# boardv2AnalogConnectors.net
KiCad netlist of a schematic drawn in EAGLE
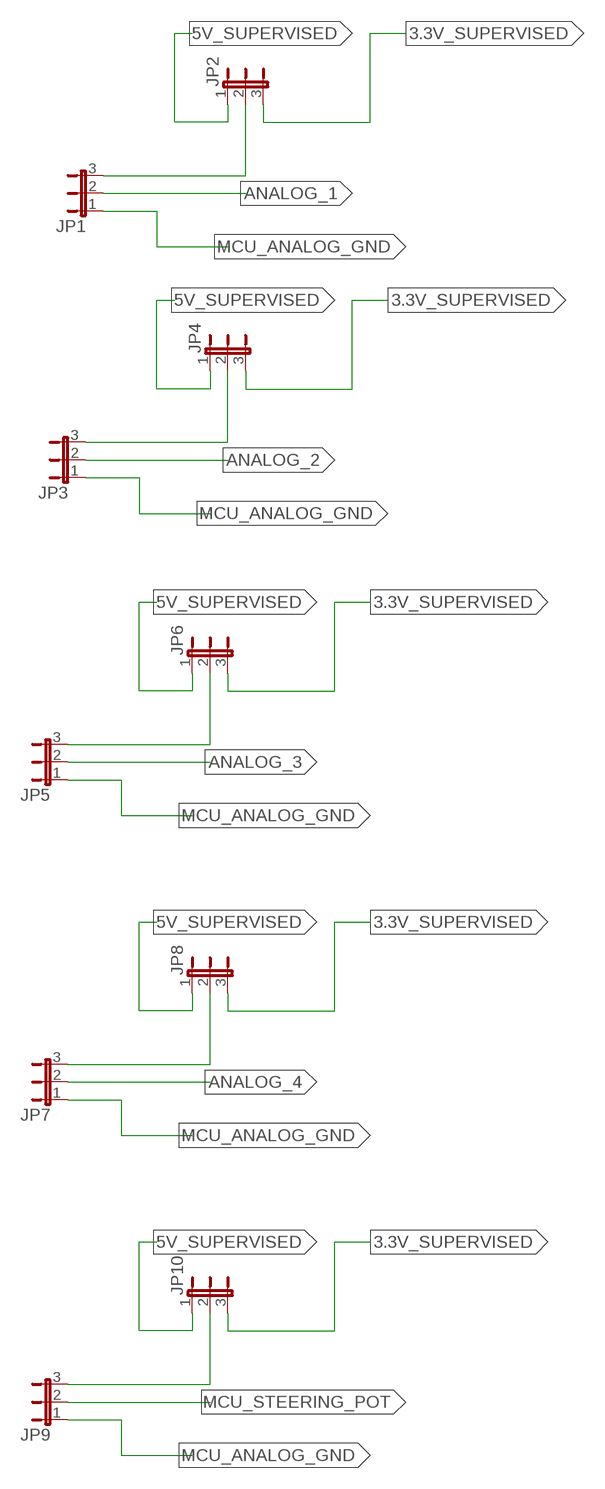
[diagram p0: schematic, sheet 1]

(export (version "E")
  (design (tool "Eeschema 10.0.6"))
  (components
    (comp (ref "JP1")
      (value "JP2E")
      (footprint "eagle-import:JP2")
      (libsource (lib "eagle-import") (part "JP2E"))
    )
    (comp (ref "JP2")
      (value "JP2E")
      (footprint "eagle-import:JP2")
      (libsource (lib "eagle-import") (part "JP2E"))
    )
    (comp (ref "JP3")
      (value "JP2E")
      (footprint "eagle-import:JP2")
      (libsource (lib "eagle-import") (part "JP2E"))
    )
    (comp (ref "JP4")
      (value "JP2E")
      (footprint "eagle-import:JP2")
      (libsource (lib "eagle-import") (part "JP2E"))
    )
    (comp (ref "JP5")
      (value "JP2E")
      (footprint "eagle-import:JP2")
      (libsource (lib "eagle-import") (part "JP2E"))
    )
    (comp (ref "JP6")
      (value "JP2E")
      (footprint "eagle-import:JP2")
      (libsource (lib "eagle-import") (part "JP2E"))
    )
    (comp (ref "JP7")
      (value "JP2E")
      (footprint "eagle-import:JP2")
      (libsource (lib "eagle-import") (part "JP2E"))
    )
    (comp (ref "JP8")
      (value "JP2E")
      (footprint "eagle-import:JP2")
      (libsource (lib "eagle-import") (part "JP2E"))
    )
    (comp (ref "JP9")
      (value "JP2E")
      (footprint "eagle-import:JP2")
      (libsource (lib "eagle-import") (part "JP2E"))
    )
    (comp (ref "JP10")
      (value "JP2E")
      (footprint "eagle-import:JP2")
      (libsource (lib "eagle-import") (part "JP2E"))
    )
  )
  (nets
    (net (code "1") (name "3.3V_SUPERVISED") (class "Default")
      (node (ref "JP10") (pin "3") (pinfunction "3_3") (pintype "passive"))
      (node (ref "JP2") (pin "3") (pinfunction "3_3") (pintype "passive"))
      (node (ref "JP4") (pin "3") (pinfunction "3_3") (pintype "passive"))
      (node (ref "JP6") (pin "3") (pinfunction "3_3") (pintype "passive"))
      (node (ref "JP8") (pin "3") (pinfunction "3_3") (pintype "passive"))
    )
    (net (code "2") (name "5V_SUPERVISED") (class "Default")
      (node (ref "JP10") (pin "1") (pinfunction "1_1") (pintype "passive"))
      (node (ref "JP2") (pin "1") (pinfunction "1_1") (pintype "passive"))
      (node (ref "JP4") (pin "1") (pinfunction "1_1") (pintype "passive"))
      (node (ref "JP6") (pin "1") (pinfunction "1_1") (pintype "passive"))
      (node (ref "JP8") (pin "1") (pinfunction "1_1") (pintype "passive"))
    )
    (net (code "3") (name "ANALOG_1") (class "Default")
      (node (ref "JP1") (pin "2") (pinfunction "2_2") (pintype "passive"))
    )
    (net (code "4") (name "ANALOG_2") (class "Default")
      (node (ref "JP3") (pin "2") (pinfunction "2_2") (pintype "passive"))
    )
    (net (code "5") (name "ANALOG_3") (class "Default")
      (node (ref "JP5") (pin "2") (pinfunction "2_2") (pintype "passive"))
    )
    (net (code "6") (name "ANALOG_4") (class "Default")
      (node (ref "JP7") (pin "2") (pinfunction "2_2") (pintype "passive"))
    )
    (net (code "7") (name "MCU_ANALOG_GND") (class "Default")
      (node (ref "JP1") (pin "1") (pinfunction "1_1") (pintype "passive"))
      (node (ref "JP3") (pin "1") (pinfunction "1_1") (pintype "passive"))
      (node (ref "JP5") (pin "1") (pinfunction "1_1") (pintype "passive"))
      (node (ref "JP7") (pin "1") (pinfunction "1_1") (pintype "passive"))
      (node (ref "JP9") (pin "1") (pinfunction "1_1") (pintype "passive"))
    )
    (net (code "8") (name "MCU_STEERING_POT") (class "Default")
      (node (ref "JP9") (pin "2") (pinfunction "2_2") (pintype "passive"))
    )
    (net (code "9") (name "Net-(JP1-Pad3)") (class "Default")
      (node (ref "JP1") (pin "3") (pinfunction "3_3") (pintype "passive"))
      (node (ref "JP2") (pin "2") (pinfunction "2_2") (pintype "passive"))
    )
    (net (code "10") (name "Net-(JP3-Pad3)") (class "Default")
      (node (ref "JP3") (pin "3") (pinfunction "3_3") (pintype "passive"))
      (node (ref "JP4") (pin "2") (pinfunction "2_2") (pintype "passive"))
    )
    (net (code "11") (name "Net-(JP5-Pad3)") (class "Default")
      (node (ref "JP5") (pin "3") (pinfunction "3_3") (pintype "passive"))
      (node (ref "JP6") (pin "2") (pinfunction "2_2") (pintype "passive"))
    )
    (net (code "12") (name "Net-(JP7-Pad3)") (class "Default")
      (node (ref "JP7") (pin "3") (pinfunction "3_3") (pintype "passive"))
      (node (ref "JP8") (pin "2") (pinfunction "2_2") (pintype "passive"))
    )
    (net (code "13") (name "Net-(JP10-Pad2)") (class "Default")
      (node (ref "JP10") (pin "2") (pinfunction "2_2") (pintype "passive"))
      (node (ref "JP9") (pin "3") (pinfunction "3_3") (pintype "passive"))
    )
  )
)
